# freq_count.net
KiCad netlist of a schematic drawn in EAGLE
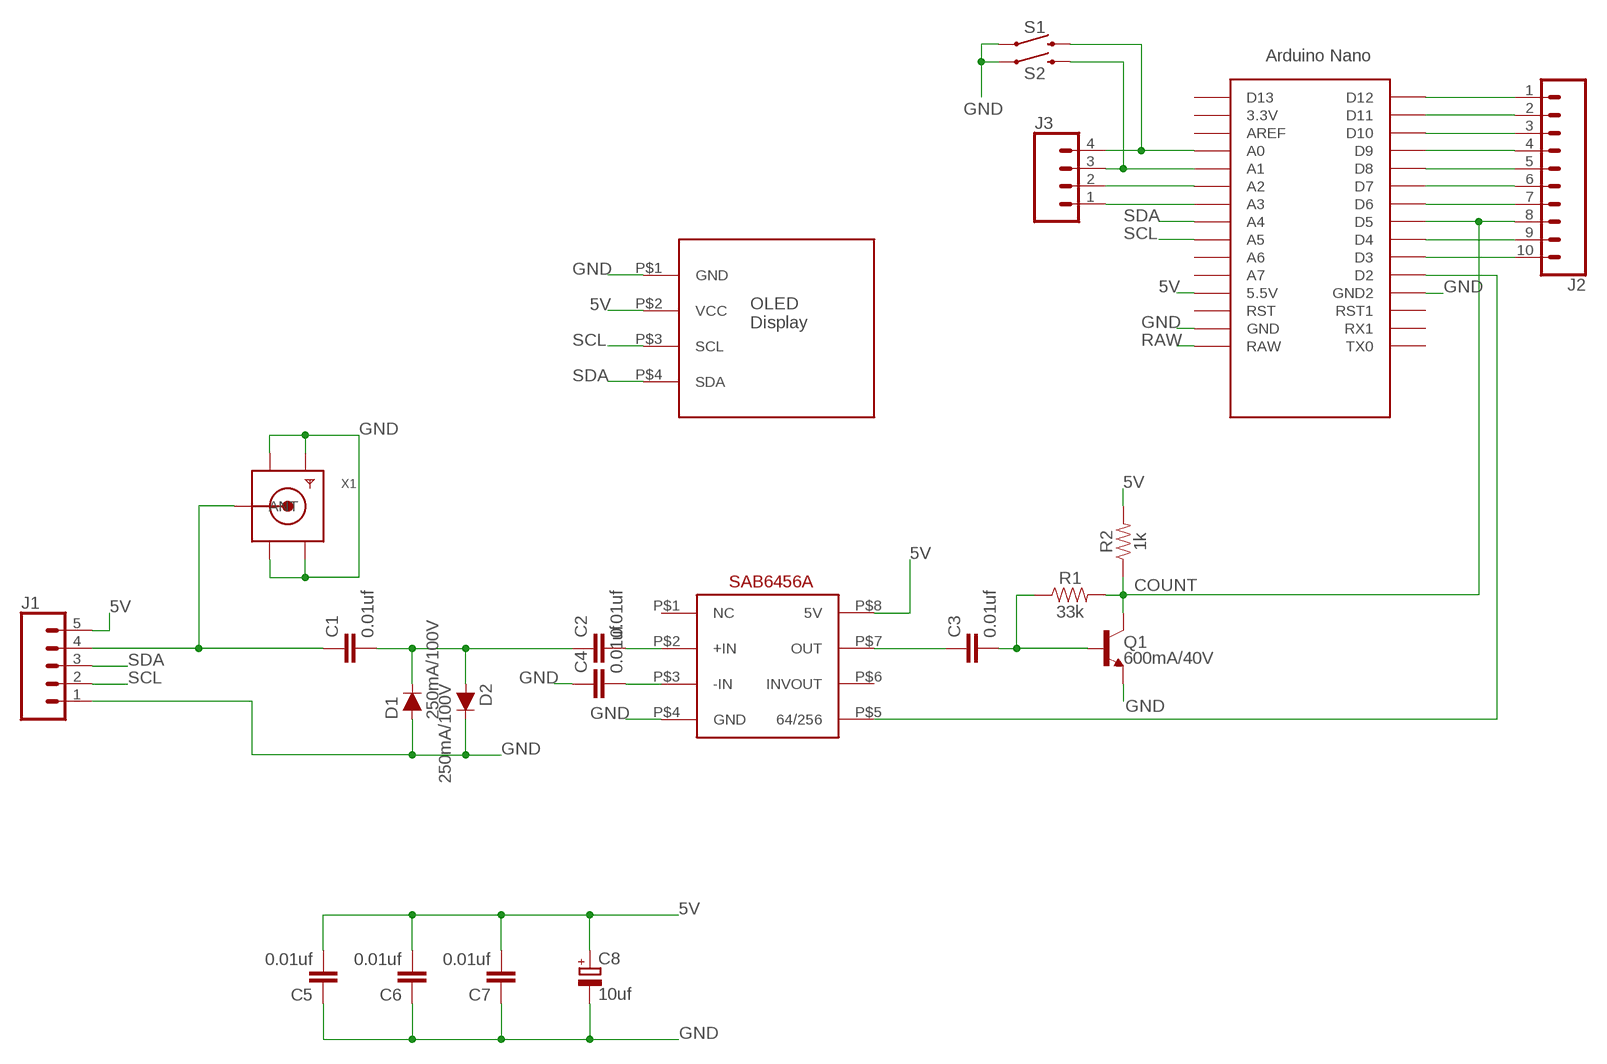
[diagram p0: schematic, sheet 1]

(export (version "E")
  (design (tool "Eeschema 10.0.6"))
  (components
    (comp (ref "C1")
      (value "0.01uf")
      (footprint "eagle-import:0805")
      (libsource (lib "eagle-import") (part "CAP0805"))
    )
    (comp (ref "C2")
      (value "0.01uf")
      (footprint "eagle-import:0805")
      (libsource (lib "eagle-import") (part "CAP0805"))
    )
    (comp (ref "C3")
      (value "0.01uf")
      (footprint "eagle-import:0805")
      (libsource (lib "eagle-import") (part "CAP0805"))
    )
    (comp (ref "C4")
      (value "0.01uf")
      (footprint "eagle-import:0805")
      (libsource (lib "eagle-import") (part "CAP0805"))
    )
    (comp (ref "C5")
      (value "0.01uf")
      (footprint "eagle-import:0805")
      (libsource (lib "eagle-import") (part "CAP0805"))
    )
    (comp (ref "C6")
      (value "0.01uf")
      (footprint "eagle-import:0805")
      (libsource (lib "eagle-import") (part "CAP0805"))
    )
    (comp (ref "C7")
      (value "0.01uf")
      (footprint "eagle-import:0805")
      (libsource (lib "eagle-import") (part "CAP0805"))
    )
    (comp (ref "C8")
      (value "10uf")
      (footprint "eagle-import:CAPMP6032X280N")
      (libsource (lib "eagle-import") (part "C-POLTANTALUM-2412(6032-METRIC)_"))
    )
    (comp (ref "D1")
      (value "250mA/100V")
      (footprint "eagle-import:SOD-323")
      (libsource (lib "eagle-import") (part "DIODE-BAS16J"))
    )
    (comp (ref "D2")
      (value "250mA/100V")
      (footprint "eagle-import:SOD-323")
      (libsource (lib "eagle-import") (part "DIODE-BAS16J"))
    )
    (comp (ref "J1")
      (value "CONN_05PTH_LONGPADS")
      (footprint "eagle-import:1X05_LONGPADS")
      (libsource (lib "eagle-import") (part "CONN_05PTH_LONGPADS"))
    )
    (comp (ref "J2")
      (value "CONN_10\"")
      (footprint "eagle-import:1X10")
      (libsource (lib "eagle-import") (part "CONN_10{dblquote}"))
    )
    (comp (ref "J3")
      (value "CONN_04")
      (footprint "eagle-import:1X04")
      (libsource (lib "eagle-import") (part "CONN_04"))
    )
    (comp (ref "Q1")
      (value "600mA/40V")
      (footprint "eagle-import:SOT23-3")
      (libsource (lib "eagle-import") (part "TRANS_NPN-MMBT2222AL"))
    )
    (comp (ref "R1")
      (value "33k")
      (footprint "eagle-import:0805")
      (libsource (lib "eagle-import") (part "RESISTOR"))
    )
    (comp (ref "R2")
      (value "1k")
      (footprint "eagle-import:0805")
      (libsource (lib "eagle-import") (part "RESISTOR"))
    )
    (comp (ref "S1")
      (value "MOMENTARY-SWITCH-SPST-PTH-6.0MM")
      (footprint "eagle-import:TACTILE_SWITCH_PTH_6.0MM")
      (libsource (lib "eagle-import") (part "MOMENTARY-SWITCH-SPST-PTH-6.0MM"))
    )
    (comp (ref "S2")
      (value "MOMENTARY-SWITCH-SPST-PTH-6.0MM")
      (footprint "eagle-import:TACTILE_SWITCH_PTH_6.0MM")
      (libsource (lib "eagle-import") (part "MOMENTARY-SWITCH-SPST-PTH-6.0MM"))
    )
    (comp (ref "U$1")
      (value "NANO")
      (footprint "eagle-import:NANO")
      (libsource (lib "eagle-import") (part "NANO"))
    )
    (comp (ref "U$2")
      (value "SAB6456A")
      (footprint "eagle-import:SAB6456A")
      (libsource (lib "eagle-import") (part "SAB6456A"))
    )
    (comp (ref "U$3")
      (value "OLED12864")
      (footprint "eagle-import:OLED12864")
      (libsource (lib "eagle-import") (part "OLED12864"))
    )
    (comp (ref "X1")
      (value "SMACONNECTOR_EDGE")
      (footprint "eagle-import:SMA_EDGELAUNCH")
      (libsource (lib "eagle-import") (part "SMACONNECTOR_EDGE"))
    )
  )
  (nets
    (net (code "1") (name "/5V") (class "Default")
      (node (ref "C5") (pin "2") (pinfunction "2_2") (pintype "passive"))
      (node (ref "C6") (pin "2") (pinfunction "2_2") (pintype "passive"))
      (node (ref "C7") (pin "2") (pinfunction "2_2") (pintype "passive"))
      (node (ref "C8") (pin "1") (pinfunction "+_1") (pintype "passive"))
      (node (ref "J1") (pin "5") (pinfunction "5_5") (pintype "passive"))
      (node (ref "R2") (pin "2") (pinfunction "2_2") (pintype "passive"))
      (node (ref "U$1") (pin "5V") (pinfunction "5.5V_5V") (pintype "bidirectional"))
      (node (ref "U$2") (pin "P$8") (pinfunction "5V_P$8") (pintype "bidirectional"))
      (node (ref "U$3") (pin "P$2") (pinfunction "VCC_P$2") (pintype "bidirectional"))
    )
    (net (code "2") (name "/COUNT") (class "Default")
      (node (ref "J2") (pin "8") (pinfunction "8_8") (pintype "passive"))
      (node (ref "Q1") (pin "3") (pinfunction "C_3") (pintype "passive"))
      (node (ref "R1") (pin "2") (pinfunction "2_2") (pintype "passive"))
      (node (ref "R2") (pin "1") (pinfunction "1_1") (pintype "passive"))
      (node (ref "U$1") (pin "D5") (pinfunction "D5_D5") (pintype "bidirectional"))
    )
    (net (code "3") (name "/GND") (class "Default")
      (node (ref "C4") (pin "1") (pinfunction "1_1") (pintype "passive"))
      (node (ref "C5") (pin "1") (pinfunction "1_1") (pintype "passive"))
      (node (ref "C6") (pin "1") (pinfunction "1_1") (pintype "passive"))
      (node (ref "C7") (pin "1") (pinfunction "1_1") (pintype "passive"))
      (node (ref "C8") (pin "2") (pinfunction "-_2") (pintype "passive"))
      (node (ref "D1") (pin "A") (pinfunction "A_A") (pintype "passive"))
      (node (ref "D2") (pin "C") (pinfunction "C_C") (pintype "passive"))
      (node (ref "J1") (pin "1") (pinfunction "1_1") (pintype "passive"))
      (node (ref "Q1") (pin "2") (pinfunction "E_2") (pintype "passive"))
      (node (ref "S1") (pin "1") (pinfunction "1_1") (pintype "passive"))
      (node (ref "S2") (pin "1") (pinfunction "1_1") (pintype "passive"))
      (node (ref "U$1") (pin "GND") (pinfunction "GND_GND") (pintype "bidirectional"))
      (node (ref "U$1") (pin "GND1") (pinfunction "GND2_GND1") (pintype "bidirectional"))
      (node (ref "U$2") (pin "P$4") (pinfunction "GND_P$4") (pintype "bidirectional"))
      (node (ref "U$3") (pin "P$1") (pinfunction "GND_P$1") (pintype "bidirectional"))
      (node (ref "X1") (pin "GND@1") (pinfunction "GND4_GND@1") (pintype "power_in"))
      (node (ref "X1") (pin "GND@2") (pinfunction "GND3_GND@2") (pintype "power_in"))
      (node (ref "X1") (pin "GND@3") (pinfunction "GND2_GND@3") (pintype "power_in"))
      (node (ref "X1") (pin "GND@4") (pinfunction "GND1_GND@4") (pintype "power_in"))
    )
    (net (code "4") (name "/RAW") (class "Default")
      (node (ref "U$1") (pin "RAW") (pinfunction "RAW_RAW") (pintype "bidirectional"))
    )
    (net (code "5") (name "/SCL") (class "Default")
      (node (ref "J1") (pin "2") (pinfunction "2_2") (pintype "passive"))
      (node (ref "U$1") (pin "A5") (pinfunction "A5_A5") (pintype "bidirectional"))
      (node (ref "U$3") (pin "P$3") (pinfunction "SCL_P$3") (pintype "bidirectional"))
    )
    (net (code "6") (name "/SDA") (class "Default")
      (node (ref "J1") (pin "3") (pinfunction "3_3") (pintype "passive"))
      (node (ref "U$1") (pin "A4") (pinfunction "A4_A4") (pintype "bidirectional"))
      (node (ref "U$3") (pin "P$4") (pinfunction "SDA_P$4") (pintype "bidirectional"))
    )
    (net (code "7") (name "Net-(C1-Pad2)") (class "Default")
      (node (ref "C1") (pin "2") (pinfunction "2_2") (pintype "passive"))
      (node (ref "C2") (pin "1") (pinfunction "1_1") (pintype "passive"))
      (node (ref "D1") (pin "C") (pinfunction "C_C") (pintype "passive"))
      (node (ref "D2") (pin "A") (pinfunction "A_A") (pintype "passive"))
    )
    (net (code "8") (name "Net-(J2-Pad1)") (class "Default")
      (node (ref "J2") (pin "1") (pinfunction "1_1") (pintype "passive"))
      (node (ref "U$1") (pin "D12") (pinfunction "D12_D12") (pintype "bidirectional"))
    )
    (net (code "9") (name "Net-(J2-Pad2)") (class "Default")
      (node (ref "J2") (pin "2") (pinfunction "2_2") (pintype "passive"))
      (node (ref "U$1") (pin "D11") (pinfunction "D11_D11") (pintype "bidirectional"))
    )
    (net (code "10") (name "Net-(J2-Pad3)") (class "Default")
      (node (ref "J2") (pin "3") (pinfunction "3_3") (pintype "passive"))
      (node (ref "U$1") (pin "D10") (pinfunction "D10_D10") (pintype "bidirectional"))
    )
    (net (code "11") (name "Net-(J2-Pad4)") (class "Default")
      (node (ref "J2") (pin "4") (pinfunction "4_4") (pintype "passive"))
      (node (ref "U$1") (pin "D9") (pinfunction "D9_D9") (pintype "bidirectional"))
    )
    (net (code "12") (name "Net-(J2-Pad5)") (class "Default")
      (node (ref "J2") (pin "5") (pinfunction "5_5") (pintype "passive"))
      (node (ref "U$1") (pin "D8") (pinfunction "D8_D8") (pintype "bidirectional"))
    )
    (net (code "13") (name "Net-(J2-Pad6)") (class "Default")
      (node (ref "J2") (pin "6") (pinfunction "6_6") (pintype "passive"))
      (node (ref "U$1") (pin "D7") (pinfunction "D7_D7") (pintype "bidirectional"))
    )
    (net (code "14") (name "Net-(J2-Pad7)") (class "Default")
      (node (ref "J2") (pin "7") (pinfunction "7_7") (pintype "passive"))
      (node (ref "U$1") (pin "D6") (pinfunction "D6_D6") (pintype "bidirectional"))
    )
    (net (code "15") (name "Net-(J2-Pad9)") (class "Default")
      (node (ref "J2") (pin "9") (pinfunction "9_9") (pintype "passive"))
      (node (ref "U$1") (pin "D4") (pinfunction "D4_D4") (pintype "bidirectional"))
    )
    (net (code "16") (name "Net-(J2-Pad10)") (class "Default")
      (node (ref "J2") (pin "10") (pinfunction "10_10") (pintype "passive"))
      (node (ref "U$1") (pin "D3") (pinfunction "D3_D3") (pintype "bidirectional"))
    )
    (net (code "17") (name "Net-(J3-Pad1)") (class "Default")
      (node (ref "J3") (pin "1") (pinfunction "1_1") (pintype "passive"))
      (node (ref "U$1") (pin "A3") (pinfunction "A3_A3") (pintype "bidirectional"))
    )
    (net (code "18") (name "Net-(J3-Pad2)") (class "Default")
      (node (ref "J3") (pin "2") (pinfunction "2_2") (pintype "passive"))
      (node (ref "U$1") (pin "A2") (pinfunction "A2_A2") (pintype "bidirectional"))
    )
    (net (code "19") (name "Net-(Q1-B)") (class "Default")
      (node (ref "C3") (pin "2") (pinfunction "2_2") (pintype "passive"))
      (node (ref "Q1") (pin "1") (pinfunction "B_1") (pintype "passive"))
      (node (ref "R1") (pin "1") (pinfunction "1_1") (pintype "passive"))
    )
    (net (code "20") (name "Net-(S1-2)") (class "Default")
      (node (ref "J3") (pin "4") (pinfunction "4_4") (pintype "passive"))
      (node (ref "S1") (pin "3") (pinfunction "2_3") (pintype "passive"))
      (node (ref "U$1") (pin "A0") (pinfunction "A0_A0") (pintype "bidirectional"))
    )
    (net (code "21") (name "Net-(S2-2)") (class "Default")
      (node (ref "J3") (pin "3") (pinfunction "3_3") (pintype "passive"))
      (node (ref "S2") (pin "3") (pinfunction "2_3") (pintype "passive"))
      (node (ref "U$1") (pin "A1") (pinfunction "A1_A1") (pintype "bidirectional"))
    )
    (net (code "22") (name "Net-(U$2-+IN)") (class "Default")
      (node (ref "C2") (pin "2") (pinfunction "2_2") (pintype "passive"))
      (node (ref "U$2") (pin "P$2") (pinfunction "+IN_P$2") (pintype "bidirectional"))
    )
    (net (code "23") (name "Net-(U$2--IN)") (class "Default")
      (node (ref "C4") (pin "2") (pinfunction "2_2") (pintype "passive"))
      (node (ref "U$2") (pin "P$3") (pinfunction "-IN_P$3") (pintype "bidirectional"))
    )
    (net (code "24") (name "Net-(U$2-64{slash}256)") (class "Default")
      (node (ref "U$1") (pin "D2") (pinfunction "D2_D2") (pintype "bidirectional"))
      (node (ref "U$2") (pin "P$5") (pinfunction "64/256_P$5") (pintype "bidirectional"))
    )
    (net (code "25") (name "Net-(U$2-OUT)") (class "Default")
      (node (ref "C3") (pin "1") (pinfunction "1_1") (pintype "passive"))
      (node (ref "U$2") (pin "P$7") (pinfunction "OUT_P$7") (pintype "bidirectional"))
    )
    (net (code "26") (name "Net-(X1-ANT)") (class "Default")
      (node (ref "C1") (pin "1") (pinfunction "1_1") (pintype "passive"))
      (node (ref "J1") (pin "4") (pinfunction "4_4") (pintype "passive"))
      (node (ref "X1") (pin "P") (pinfunction "ANT_P") (pintype "bidirectional"))
    )
    (net (code "27") (name "unconnected-(U$1-Pad3.3V)") (class "Default")
      (node (ref "U$1") (pin "3.3V") (pinfunction "3.3V_3.3V") (pintype "bidirectional"))
    )
    (net (code "28") (name "unconnected-(U$1-PadA6)") (class "Default")
      (node (ref "U$1") (pin "A6") (pinfunction "A6_A6") (pintype "bidirectional"))
    )
    (net (code "29") (name "unconnected-(U$1-PadA7)") (class "Default")
      (node (ref "U$1") (pin "A7") (pinfunction "A7_A7") (pintype "bidirectional"))
    )
    (net (code "30") (name "unconnected-(U$1-PadAREF)") (class "Default")
      (node (ref "U$1") (pin "AREF") (pinfunction "AREF_AREF") (pintype "bidirectional"))
    )
    (net (code "31") (name "unconnected-(U$1-PadD13)") (class "Default")
      (node (ref "U$1") (pin "D13") (pinfunction "D13_D13") (pintype "bidirectional"))
    )
    (net (code "32") (name "unconnected-(U$1-PadICSP1)") (class "Default")
      (node (ref "U$1") (pin "ICSP1") (pinfunction "ICSP1_ICSP1") (pintype "bidirectional"))
    )
    (net (code "33") (name "unconnected-(U$1-PadICSP2)") (class "Default")
      (node (ref "U$1") (pin "ICSP2") (pinfunction "ICSP2_ICSP2") (pintype "bidirectional"))
    )
    (net (code "34") (name "unconnected-(U$1-PadICSP3)") (class "Default")
      (node (ref "U$1") (pin "ICSP3") (pinfunction "ICSP3_ICSP3") (pintype "bidirectional"))
    )
    (net (code "35") (name "unconnected-(U$1-PadICSP4)") (class "Default")
      (node (ref "U$1") (pin "ICSP4") (pinfunction "ICSP4_ICSP4") (pintype "bidirectional"))
    )
    (net (code "36") (name "unconnected-(U$1-PadICSP5)") (class "Default")
      (node (ref "U$1") (pin "ICSP5") (pinfunction "ICSP5_ICSP5") (pintype "bidirectional"))
    )
    (net (code "37") (name "unconnected-(U$1-PadICSP6)") (class "Default")
      (node (ref "U$1") (pin "ICSP6") (pinfunction "ICSP6_ICSP6") (pintype "bidirectional"))
    )
    (net (code "38") (name "unconnected-(U$1-PadRST)") (class "Default")
      (node (ref "U$1") (pin "RST") (pinfunction "RST_RST") (pintype "bidirectional"))
    )
    (net (code "39") (name "unconnected-(U$1-PadRST1)") (class "Default")
      (node (ref "U$1") (pin "RST1") (pinfunction "RST1_RST1") (pintype "bidirectional"))
    )
    (net (code "40") (name "unconnected-(U$1-PadRX1)") (class "Default")
      (node (ref "U$1") (pin "RX1") (pinfunction "RX1_RX1") (pintype "bidirectional"))
    )
    (net (code "41") (name "unconnected-(U$1-PadTX0)") (class "Default")
      (node (ref "U$1") (pin "TX0") (pinfunction "TX0_TX0") (pintype "bidirectional"))
    )
    (net (code "42") (name "unconnected-(U$2-INVOUT-PadP$6)") (class "Default")
      (node (ref "U$2") (pin "P$6") (pinfunction "INVOUT_P$6") (pintype "bidirectional"))
    )
    (net (code "43") (name "unconnected-(U$2-NC-PadP$1)") (class "Default")
      (node (ref "U$2") (pin "P$1") (pinfunction "NC_P$1") (pintype "bidirectional"))
    )
  )
)
